# Rx_micro.net
KiCad netlist of a schematic drawn in Altium Designer
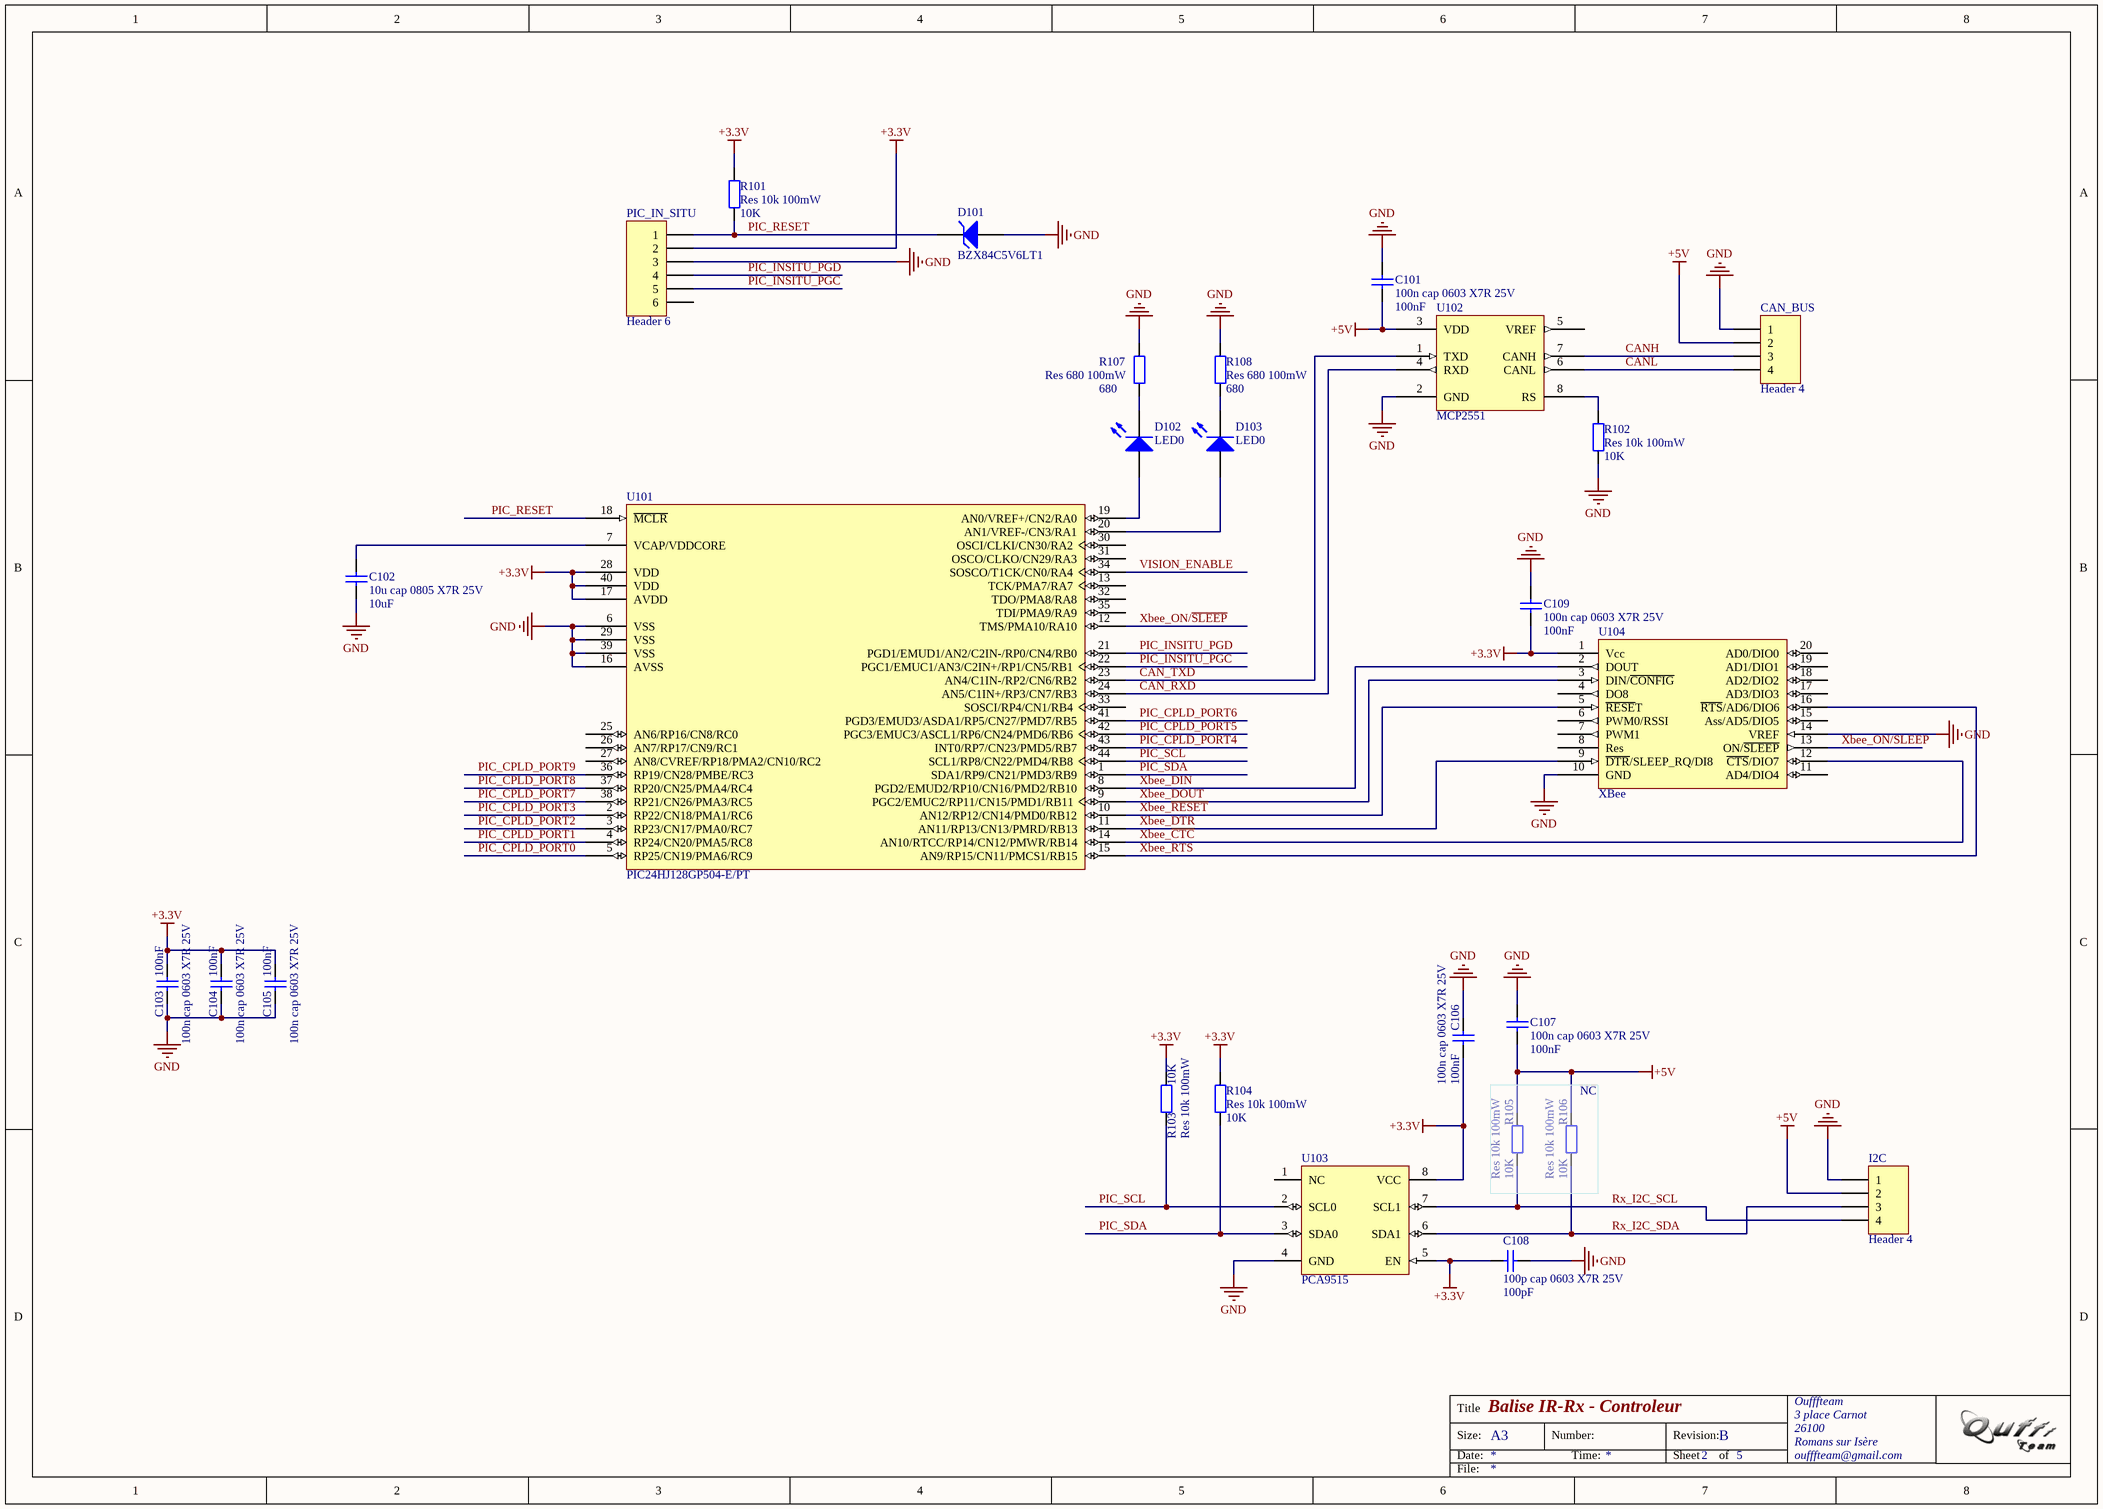
[diagram p0: Rx_micro.SchDoc]

(export (version "E")
  (design (tool "Eeschema 10.0.6"))
  (components
    (comp (ref "C101")
      (value "100n cap 0603 X7R 25V")
      (footprint "0603")
      (description "Capacitor")
      (fields (field (name "ALTIUM_VALUE") "100nF") (field (name "PUBLISHER") "Altium Limited"))
      (libsource (lib "Miscellaneous Devices") (part "Cap"))
    )
    (comp (ref "C102")
      (value "10u cap 0805 X7R 25V")
      (footprint "0805")
      (description "Capacitor")
      (fields (field (name "ALTIUM_VALUE") "10uF") (field (name "PUBLISHER") "Altium Limited"))
      (libsource (lib "Miscellaneous Devices") (part "Cap"))
    )
    (comp (ref "C103")
      (value "100n cap 0603 X7R 25V")
      (footprint "0603")
      (description "Capacitor")
      (fields (field (name "ALTIUM_VALUE") "100nF") (field (name "PUBLISHER") "Altium Limited"))
      (libsource (lib "Miscellaneous Devices") (part "Cap"))
    )
    (comp (ref "C104")
      (value "100n cap 0603 X7R 25V")
      (footprint "0603")
      (description "Capacitor")
      (fields (field (name "ALTIUM_VALUE") "100nF") (field (name "PUBLISHER") "Altium Limited"))
      (libsource (lib "Miscellaneous Devices") (part "Cap"))
    )
    (comp (ref "C105")
      (value "100n cap 0603 X7R 25V")
      (footprint "0603")
      (description "Capacitor")
      (fields (field (name "ALTIUM_VALUE") "100nF") (field (name "PUBLISHER") "Altium Limited"))
      (libsource (lib "Miscellaneous Devices") (part "Cap"))
    )
    (comp (ref "C106")
      (value "100n cap 0603 X7R 25V")
      (footprint "1608[0603]")
      (description "Capacitor")
      (fields (field (name "ALTIUM_VALUE") "100nF") (field (name "PUBLISHER") "Altium Limited"))
      (libsource (lib "Miscellaneous Devices") (part "Cap"))
    )
    (comp (ref "C107")
      (value "100n cap 0603 X7R 25V")
      (footprint "1608[0603]")
      (description "Capacitor")
      (fields (field (name "ALTIUM_VALUE") "100nF") (field (name "PUBLISHER") "Altium Limited"))
      (libsource (lib "Miscellaneous Devices") (part "Cap"))
    )
    (comp (ref "C108")
      (value "100p cap 0603 X7R 25V")
      (footprint "1608[0603]")
      (description "Capacitor")
      (fields (field (name "ALTIUM_VALUE") "100pF") (field (name "PUBLISHER") "Altium Limited"))
      (libsource (lib "Miscellaneous Devices") (part "Cap"))
    )
    (comp (ref "C109")
      (value "100n cap 0603 X7R 25V")
      (footprint "0603")
      (description "Capacitor")
      (fields (field (name "ALTIUM_VALUE") "100nF") (field (name "PUBLISHER") "Altium Limited"))
      (libsource (lib "Miscellaneous Devices") (part "Cap"))
    )
    (comp (ref "CAN_BUS")
      (value "Header 4")
      (footprint "HDR1X4")
      (description "Header, 4-Pin")
      (fields (field (name "PUBLISHER") "Altium Limited"))
      (libsource (lib "Miscellaneous Connectors") (part "Header 4"))
    )
    (comp (ref "D101")
      (value "BZX84C5V6LT1")
      (footprint "318-07")
      (description "Zener Voltage Regulator Diode")
      (fields (field (name "PUBLISHER") "Altium Limited"))
      (libsource (lib "Motorola Discrete Diode") (part "BZX84C5V6LT1"))
    )
    (comp (ref "D102")
      (value "LED0")
      (footprint "0603")
      (description "0603 Led")
      (fields (field (name "PUBLISHER") "Altium Limited"))
      (libsource (lib "Miscellaneous Devices") (part "LED0"))
    )
    (comp (ref "D103")
      (value "LED0")
      (footprint "0603")
      (description "0603 Led")
      (fields (field (name "PUBLISHER") "Altium Limited"))
      (libsource (lib "Miscellaneous Devices") (part "LED0"))
    )
    (comp (ref "I2C")
      (value "Header 4")
      (footprint "HDR1X4")
      (description "Header, 4-Pin")
      (fields (field (name "PUBLISHER") "Altium Limited"))
      (libsource (lib "Miscellaneous Connectors") (part "Header 4"))
    )
    (comp (ref "PIC_IN_SITU")
      (value "Header 6")
      (footprint "HDR1X6")
      (description "Header, 6-Pin")
      (fields (field (name "PUBLISHER") "Altium Limited"))
      (libsource (lib "Miscellaneous Connectors") (part "Header 6"))
    )
    (comp (ref "R101")
      (value "Res 10k 100mW")
      (footprint "0603")
      (description "Resistor")
      (fields (field (name "ALTIUM_VALUE") "10K") (field (name "PUBLISHER") "Altium Limited"))
      (libsource (lib "Miscellaneous Devices") (part "Res2"))
    )
    (comp (ref "R102")
      (value "Res 10k 100mW")
      (footprint "0603")
      (description "Resistor")
      (fields (field (name "ALTIUM_VALUE") "10K") (field (name "PUBLISHER") "Altium Limited"))
      (libsource (lib "Miscellaneous Devices") (part "Res2"))
    )
    (comp (ref "R103")
      (value "Res 10k 100mW")
      (footprint "0603")
      (description "Resistor")
      (fields (field (name "ALTIUM_VALUE") "10K") (field (name "PUBLISHER") "Altium Limited"))
      (libsource (lib "Miscellaneous Devices") (part "Res2"))
    )
    (comp (ref "R104")
      (value "Res 10k 100mW")
      (footprint "0603")
      (description "Resistor")
      (fields (field (name "ALTIUM_VALUE") "10K") (field (name "PUBLISHER") "Altium Limited"))
      (libsource (lib "Miscellaneous Devices") (part "Res2"))
    )
    (comp (ref "R105")
      (value "Res 10k 100mW")
      (footprint "1608[0603]")
      (description "Resistor")
      (fields (field (name "ALTIUM_VALUE") "10K") (field (name "PUBLISHER") "Altium Limited"))
      (libsource (lib "Miscellaneous Devices") (part "Res2"))
    )
    (comp (ref "R106")
      (value "Res 10k 100mW")
      (footprint "1608[0603]")
      (description "Resistor")
      (fields (field (name "ALTIUM_VALUE") "10K") (field (name "PUBLISHER") "Altium Limited"))
      (libsource (lib "Miscellaneous Devices") (part "Res2"))
    )
    (comp (ref "R107")
      (value "Res 680 100mW")
      (footprint "0603")
      (description "Resistor")
      (fields (field (name "ALTIUM_VALUE") "680") (field (name "PUBLISHER") "Altium Limited"))
      (libsource (lib "Miscellaneous Devices") (part "Res2"))
    )
    (comp (ref "R108")
      (value "Res 680 100mW")
      (footprint "0603")
      (description "Resistor")
      (fields (field (name "ALTIUM_VALUE") "680") (field (name "PUBLISHER") "Altium Limited"))
      (libsource (lib "Miscellaneous Devices") (part "Res2"))
    )
    (comp (ref "U101")
      (value "PIC24HJ128GP504-E/PT")
      (footprint "TQFP-PT44_N")
      (fields (field (name "PUBLISHER") "Altium Limited"))
      (libsource (lib "Microchip Microcontroller 16-Bit PIC24H") (part "PIC24HJ128GP504-E/PT"))
    )
    (comp (ref "U102")
      (value "MCP2551")
      (footprint "SOIC150-8_N")
      (description "High Speed Can Transceiver")
      (fields (field (name "PUBLISHER") "Altium Limited"))
      (libsource (lib "Microchip Interface Line Transceiver") (part "MCP2551"))
    )
    (comp (ref "U103")
      (value "PCA9515")
      (footprint "TSSOP-8")
      (description "DUAL BIDIRECTIONAL I2C BUS AND SMBus REPEATER")
      (libsource (lib "Oufff_Lib2") (part "PCA9515"))
    )
    (comp (ref "U104")
      (value "XBee")
      (footprint "XBee_SM")
      (description "OEM RF Modules")
      (libsource (lib "Oufff_Lib2") (part "XBee"))
    )
  )
  (nets
    (net (code "1") (name "+3.3V") (class "Default")
      (node (ref "C103") (pin "2") (pinfunction "2_2") (pintype "passive"))
      (node (ref "C104") (pin "2") (pinfunction "2_2") (pintype "passive"))
      (node (ref "C105") (pin "2") (pinfunction "2_2") (pintype "passive"))
      (node (ref "C106") (pin "1") (pinfunction "1_1") (pintype "passive"))
      (node (ref "C108") (pin "2") (pinfunction "2_2") (pintype "passive"))
      (node (ref "C109") (pin "1") (pinfunction "1_1") (pintype "passive"))
      (node (ref "PIC_IN_SITU") (pin "2") (pinfunction "2_2") (pintype "passive"))
      (node (ref "R101") (pin "2") (pinfunction "2_2") (pintype "passive"))
      (node (ref "R103") (pin "2") (pinfunction "2_2") (pintype "passive"))
      (node (ref "R104") (pin "2") (pinfunction "2_2") (pintype "passive"))
      (node (ref "U101") (pin "17") (pinfunction "AVDD_17") (pintype "power_in"))
      (node (ref "U101") (pin "28") (pinfunction "VDD_28") (pintype "power_in"))
      (node (ref "U101") (pin "40") (pinfunction "VDD_40") (pintype "power_in"))
      (node (ref "U103") (pin "5") (pinfunction "EN_5") (pintype "input"))
      (node (ref "U103") (pin "8") (pinfunction "VCC_8") (pintype "power_in"))
      (node (ref "U104") (pin "1") (pinfunction "Vcc_1") (pintype "power_in"))
    )
    (net (code "2") (name "+5V") (class "Default")
      (node (ref "C101") (pin "1") (pinfunction "1_1") (pintype "passive"))
      (node (ref "C107") (pin "2") (pinfunction "2_2") (pintype "passive"))
      (node (ref "CAN_BUS") (pin "2") (pinfunction "2_2") (pintype "passive"))
      (node (ref "I2C") (pin "2") (pinfunction "2_2") (pintype "passive"))
      (node (ref "R105") (pin "2") (pinfunction "2_2") (pintype "passive"))
      (node (ref "R106") (pin "2") (pinfunction "2_2") (pintype "passive"))
      (node (ref "U102") (pin "3") (pinfunction "VDD_3") (pintype "power_in"))
    )
    (net (code "3") (name "/CANH") (class "Default")
      (node (ref "CAN_BUS") (pin "3") (pinfunction "3_3") (pintype "passive"))
      (node (ref "U102") (pin "7") (pinfunction "CANH_7") (pintype "output"))
    )
    (net (code "4") (name "/CANL") (class "Default")
      (node (ref "CAN_BUS") (pin "4") (pinfunction "4_4") (pintype "passive"))
      (node (ref "U102") (pin "6") (pinfunction "CANL_6") (pintype "output"))
    )
    (net (code "5") (name "/CAN_RXD") (class "Default")
      (node (ref "U101") (pin "24") (pinfunction "AN5/C1IN+/RP3/CN7/RB3_24") (pintype "bidirectional"))
      (node (ref "U102") (pin "4") (pinfunction "RXD_4") (pintype "output"))
    )
    (net (code "6") (name "/CAN_TXD") (class "Default")
      (node (ref "U101") (pin "23") (pinfunction "AN4/C1IN-/RP2/CN6/RB2_23") (pintype "bidirectional"))
      (node (ref "U102") (pin "1") (pinfunction "TXD_1") (pintype "input"))
    )
    (net (code "7") (name "/PIC_CPLD_PORT0") (class "Default")
      (node (ref "U101") (pin "5") (pinfunction "RP25/CN19/PMA6/RC9_5") (pintype "bidirectional"))
    )
    (net (code "8") (name "/PIC_CPLD_PORT1") (class "Default")
      (node (ref "U101") (pin "4") (pinfunction "RP24/CN20/PMA5/RC8_4") (pintype "bidirectional"))
    )
    (net (code "9") (name "/PIC_CPLD_PORT2") (class "Default")
      (node (ref "U101") (pin "3") (pinfunction "RP23/CN17/PMA0/RC7_3") (pintype "bidirectional"))
    )
    (net (code "10") (name "/PIC_CPLD_PORT3") (class "Default")
      (node (ref "U101") (pin "2") (pinfunction "RP22/CN18/PMA1/RC6_2") (pintype "bidirectional"))
    )
    (net (code "11") (name "/PIC_CPLD_PORT4") (class "Default")
      (node (ref "U101") (pin "43") (pinfunction "INT0/RP7/CN23/PMD5/RB7_43") (pintype "bidirectional"))
    )
    (net (code "12") (name "/PIC_CPLD_PORT5") (class "Default")
      (node (ref "U101") (pin "42") (pinfunction "PGC3/EMUC3/ASCL1/RP6/CN24/PMD6/RB6_42") (pintype "bidirectional"))
    )
    (net (code "13") (name "/PIC_CPLD_PORT6") (class "Default")
      (node (ref "U101") (pin "41") (pinfunction "PGD3/EMUD3/ASDA1/RP5/CN27/PMD7/RB5_41") (pintype "bidirectional"))
    )
    (net (code "14") (name "/PIC_CPLD_PORT7") (class "Default")
      (node (ref "U101") (pin "38") (pinfunction "RP21/CN26/PMA3/RC5_38") (pintype "bidirectional"))
    )
    (net (code "15") (name "/PIC_CPLD_PORT8") (class "Default")
      (node (ref "U101") (pin "37") (pinfunction "RP20/CN25/PMA4/RC4_37") (pintype "bidirectional"))
    )
    (net (code "16") (name "/PIC_CPLD_PORT9") (class "Default")
      (node (ref "U101") (pin "36") (pinfunction "RP19/CN28/PMBE/RC3_36") (pintype "bidirectional"))
    )
    (net (code "17") (name "/PIC_INSITU_PGC") (class "Default")
      (node (ref "PIC_IN_SITU") (pin "5") (pinfunction "5_5") (pintype "passive"))
      (node (ref "U101") (pin "22") (pinfunction "PGC1/EMUC1/AN3/C2IN+/RP1/CN5/RB1_22") (pintype "bidirectional"))
    )
    (net (code "18") (name "/PIC_INSITU_PGD") (class "Default")
      (node (ref "PIC_IN_SITU") (pin "4") (pinfunction "4_4") (pintype "passive"))
      (node (ref "U101") (pin "21") (pinfunction "PGD1/EMUD1/AN2/C2IN-/RP0/CN4/RB0_21") (pintype "bidirectional"))
    )
    (net (code "19") (name "/PIC_RESET") (class "Default")
      (node (ref "D101") (pin "3") (pinfunction "K_3") (pintype "passive"))
      (node (ref "PIC_IN_SITU") (pin "1") (pinfunction "1_1") (pintype "passive"))
      (node (ref "R101") (pin "1") (pinfunction "1_1") (pintype "passive"))
      (node (ref "U101") (pin "18") (pinfunction "~{MCLR}_18") (pintype "input"))
    )
    (net (code "20") (name "/PIC_SCL") (class "Default")
      (node (ref "R103") (pin "1") (pinfunction "1_1") (pintype "passive"))
      (node (ref "U101") (pin "44") (pinfunction "SCL1/RP8/CN22/PMD4/RB8_44") (pintype "bidirectional"))
      (node (ref "U103") (pin "2") (pinfunction "SCL0_2") (pintype "bidirectional"))
    )
    (net (code "21") (name "/PIC_SDA") (class "Default")
      (node (ref "R104") (pin "1") (pinfunction "1_1") (pintype "passive"))
      (node (ref "U101") (pin "1") (pinfunction "SDA1/RP9/CN21/PMD3/RB9_1") (pintype "bidirectional"))
      (node (ref "U103") (pin "3") (pinfunction "SDA0_3") (pintype "bidirectional"))
    )
    (net (code "22") (name "/Rx_I2C_SCL") (class "Default")
      (node (ref "I2C") (pin "4") (pinfunction "4_4") (pintype "passive"))
      (node (ref "R105") (pin "1") (pinfunction "1_1") (pintype "passive"))
      (node (ref "U103") (pin "7") (pinfunction "SCL1_7") (pintype "bidirectional"))
    )
    (net (code "23") (name "/Rx_I2C_SDA") (class "Default")
      (node (ref "I2C") (pin "3") (pinfunction "3_3") (pintype "passive"))
      (node (ref "R106") (pin "1") (pinfunction "1_1") (pintype "passive"))
      (node (ref "U103") (pin "6") (pinfunction "SDA1_6") (pintype "bidirectional"))
    )
    (net (code "24") (name "/VISION_ENABLE") (class "Default")
      (node (ref "U101") (pin "34") (pinfunction "SOSCO/T1CK/CN0/RA4_34") (pintype "bidirectional"))
    )
    (net (code "25") (name "/Xbee_DIN") (class "Default")
      (node (ref "U101") (pin "8") (pinfunction "PGD2/EMUD2/RP10/CN16/PMD2/RB10_8") (pintype "bidirectional"))
      (node (ref "U104") (pin "2") (pinfunction "DOUT_2") (pintype "output"))
    )
    (net (code "26") (name "/Xbee_DOUT") (class "Default")
      (node (ref "U101") (pin "9") (pinfunction "PGC2/EMUC2/RP11/CN15/PMD1/RB11_9") (pintype "bidirectional"))
      (node (ref "U104") (pin "3") (pinfunction "DIN/~{CONFIG}_3") (pintype "input"))
    )
    (net (code "27") (name "/Xbee_DTR") (class "Default")
      (node (ref "U101") (pin "11") (pinfunction "AN11/RP13/CN13/PMRD/RB13_11") (pintype "bidirectional"))
      (node (ref "U104") (pin "9") (pinfunction "~{DTR}/SLEEP_RQ/DI8_9") (pintype "input"))
    )
    (net (code "28") (name "/Xbee_ON{slash}~{SLEEP}") (class "Default")
      (node (ref "U101") (pin "12") (pinfunction "TMS/PMA10/RA10_12") (pintype "bidirectional"))
      (node (ref "U104") (pin "13") (pinfunction "ON/~{SLEEP}_13") (pintype "output"))
    )
    (net (code "29") (name "/Xbee_~{CTC}") (class "Default")
      (node (ref "U101") (pin "14") (pinfunction "AN10/RTCC/RP14/CN12/PMWR/RB14_14") (pintype "bidirectional"))
      (node (ref "U104") (pin "12") (pinfunction "~{CTS}/DIO7_12") (pintype "bidirectional"))
    )
    (net (code "30") (name "/Xbee_~{RESET}") (class "Default")
      (node (ref "U101") (pin "10") (pinfunction "AN12/RP12/CN14/PMD0/RB12_10") (pintype "bidirectional"))
      (node (ref "U104") (pin "5") (pinfunction "~{RESE}T_5") (pintype "input"))
    )
    (net (code "31") (name "/Xbee_~{RTS}") (class "Default")
      (node (ref "U101") (pin "15") (pinfunction "AN9/RP15/CN11/PMCS1/RB15_15") (pintype "bidirectional"))
      (node (ref "U104") (pin "16") (pinfunction "~{RTS}/AD6/DIO6_16") (pintype "bidirectional"))
    )
    (net (code "32") (name "GND") (class "Default")
      (node (ref "C101") (pin "2") (pinfunction "2_2") (pintype "passive"))
      (node (ref "C102") (pin "1") (pinfunction "1_1") (pintype "passive"))
      (node (ref "C103") (pin "1") (pinfunction "1_1") (pintype "passive"))
      (node (ref "C104") (pin "1") (pinfunction "1_1") (pintype "passive"))
      (node (ref "C105") (pin "1") (pinfunction "1_1") (pintype "passive"))
      (node (ref "C106") (pin "2") (pinfunction "2_2") (pintype "passive"))
      (node (ref "C107") (pin "1") (pinfunction "1_1") (pintype "passive"))
      (node (ref "C108") (pin "1") (pinfunction "1_1") (pintype "passive"))
      (node (ref "C109") (pin "2") (pinfunction "2_2") (pintype "passive"))
      (node (ref "CAN_BUS") (pin "1") (pinfunction "1_1") (pintype "passive"))
      (node (ref "D101") (pin "1") (pinfunction "A_1") (pintype "passive"))
      (node (ref "I2C") (pin "1") (pinfunction "1_1") (pintype "passive"))
      (node (ref "PIC_IN_SITU") (pin "3") (pinfunction "3_3") (pintype "passive"))
      (node (ref "R102") (pin "1") (pinfunction "1_1") (pintype "passive"))
      (node (ref "R107") (pin "2") (pinfunction "2_2") (pintype "passive"))
      (node (ref "R108") (pin "2") (pinfunction "2_2") (pintype "passive"))
      (node (ref "U101") (pin "16") (pinfunction "AVSS_16") (pintype "power_in"))
      (node (ref "U101") (pin "29") (pinfunction "VSS_29") (pintype "power_in"))
      (node (ref "U101") (pin "39") (pinfunction "VSS_39") (pintype "power_in"))
      (node (ref "U101") (pin "6") (pinfunction "VSS_6") (pintype "power_in"))
      (node (ref "U102") (pin "2") (pinfunction "GND_2") (pintype "power_in"))
      (node (ref "U103") (pin "4") (pinfunction "GND_4") (pintype "power_in"))
      (node (ref "U104") (pin "10") (pinfunction "GND_10") (pintype "power_in"))
      (node (ref "U104") (pin "14") (pinfunction "VREF_14") (pintype "input"))
    )
    (net (code "33") (name "Net-(D102-A)") (class "Default")
      (node (ref "D102") (pin "1") (pinfunction "A_1") (pintype "passive"))
      (node (ref "U101") (pin "19") (pinfunction "AN0/VREF+/CN2/RA0_19") (pintype "bidirectional"))
    )
    (net (code "34") (name "Net-(D102-K)") (class "Default")
      (node (ref "D102") (pin "2") (pinfunction "K_2") (pintype "passive"))
      (node (ref "R107") (pin "1") (pinfunction "1_1") (pintype "passive"))
    )
    (net (code "35") (name "Net-(D103-A)") (class "Default")
      (node (ref "D103") (pin "1") (pinfunction "A_1") (pintype "passive"))
      (node (ref "U101") (pin "20") (pinfunction "AN1/VREF-/CN3/RA1_20") (pintype "bidirectional"))
    )
    (net (code "36") (name "Net-(D103-K)") (class "Default")
      (node (ref "D103") (pin "2") (pinfunction "K_2") (pintype "passive"))
      (node (ref "R108") (pin "1") (pinfunction "1_1") (pintype "passive"))
    )
    (net (code "37") (name "Net-(U101-VCAP{slash}VDDCORE)") (class "Default")
      (node (ref "C102") (pin "2") (pinfunction "2_2") (pintype "passive"))
      (node (ref "U101") (pin "7") (pinfunction "VCAP/VDDCORE_7") (pintype "power_in"))
    )
    (net (code "38") (name "Net-(U102-RS)") (class "Default")
      (node (ref "R102") (pin "2") (pinfunction "2_2") (pintype "passive"))
      (node (ref "U102") (pin "8") (pinfunction "RS_8") (pintype "passive"))
    )
    (net (code "39") (name "unconnected-(PIC_IN_SITU-Pad6)") (class "Default")
      (node (ref "PIC_IN_SITU") (pin "6") (pinfunction "6_6") (pintype "passive"))
    )
    (net (code "40") (name "unconnected-(U101-AN6{slash}RP16{slash}CN8{slash}RC0-Pad25)") (class "Default")
      (node (ref "U101") (pin "25") (pinfunction "AN6/RP16/CN8/RC0_25") (pintype "bidirectional"))
    )
    (net (code "41") (name "unconnected-(U101-AN7{slash}RP17{slash}CN9{slash}RC1-Pad26)") (class "Default")
      (node (ref "U101") (pin "26") (pinfunction "AN7/RP17/CN9/RC1_26") (pintype "bidirectional"))
    )
    (net (code "42") (name "unconnected-(U101-AN8{slash}CVREF{slash}RP18{slash}PMA2{slash}CN10{slash}RC2-Pad27)") (class "Default")
      (node (ref "U101") (pin "27") (pinfunction "AN8/CVREF/RP18/PMA2/CN10/RC2_27") (pintype "bidirectional"))
    )
    (net (code "43") (name "unconnected-(U101-OSCI{slash}CLKI{slash}CN30{slash}RA2-Pad30)") (class "Default")
      (node (ref "U101") (pin "30") (pinfunction "OSCI/CLKI/CN30/RA2_30") (pintype "bidirectional"))
    )
    (net (code "44") (name "unconnected-(U101-OSCO{slash}CLKO{slash}CN29{slash}RA3-Pad31)") (class "Default")
      (node (ref "U101") (pin "31") (pinfunction "OSCO/CLKO/CN29/RA3_31") (pintype "bidirectional"))
    )
    (net (code "45") (name "unconnected-(U101-SOSCI{slash}RP4{slash}CN1{slash}RB4-Pad33)") (class "Default")
      (node (ref "U101") (pin "33") (pinfunction "SOSCI/RP4/CN1/RB4_33") (pintype "bidirectional"))
    )
    (net (code "46") (name "unconnected-(U101-TCK{slash}PMA7{slash}RA7-Pad13)") (class "Default")
      (node (ref "U101") (pin "13") (pinfunction "TCK/PMA7/RA7_13") (pintype "bidirectional"))
    )
    (net (code "47") (name "unconnected-(U101-TDI{slash}PMA9{slash}RA9-Pad35)") (class "Default")
      (node (ref "U101") (pin "35") (pinfunction "TDI/PMA9/RA9_35") (pintype "bidirectional"))
    )
    (net (code "48") (name "unconnected-(U101-TDO{slash}PMA8{slash}RA8-Pad32)") (class "Default")
      (node (ref "U101") (pin "32") (pinfunction "TDO/PMA8/RA8_32") (pintype "bidirectional"))
    )
    (net (code "49") (name "unconnected-(U102-VREF-Pad5)") (class "Default")
      (node (ref "U102") (pin "5") (pinfunction "VREF_5") (pintype "output"))
    )
    (net (code "50") (name "unconnected-(U103-NC-Pad1)") (class "Default")
      (node (ref "U103") (pin "1") (pinfunction "NC_1") (pintype "passive"))
    )
    (net (code "51") (name "unconnected-(U104-AD0{slash}DIO0-Pad20)") (class "Default")
      (node (ref "U104") (pin "20") (pinfunction "AD0/DIO0_20") (pintype "bidirectional"))
    )
    (net (code "52") (name "unconnected-(U104-AD1{slash}DIO1-Pad19)") (class "Default")
      (node (ref "U104") (pin "19") (pinfunction "AD1/DIO1_19") (pintype "bidirectional"))
    )
    (net (code "53") (name "unconnected-(U104-AD2{slash}DIO2-Pad18)") (class "Default")
      (node (ref "U104") (pin "18") (pinfunction "AD2/DIO2_18") (pintype "bidirectional"))
    )
    (net (code "54") (name "unconnected-(U104-AD3{slash}DIO3-Pad17)") (class "Default")
      (node (ref "U104") (pin "17") (pinfunction "AD3/DIO3_17") (pintype "bidirectional"))
    )
    (net (code "55") (name "unconnected-(U104-AD4{slash}DIO4-Pad11)") (class "Default")
      (node (ref "U104") (pin "11") (pinfunction "AD4/DIO4_11") (pintype "bidirectional"))
    )
    (net (code "56") (name "unconnected-(U104-Ass{slash}AD5{slash}DIO5-Pad15)") (class "Default")
      (node (ref "U104") (pin "15") (pinfunction "Ass/AD5/DIO5_15") (pintype "bidirectional"))
    )
    (net (code "57") (name "unconnected-(U104-DO8-Pad4)") (class "Default")
      (node (ref "U104") (pin "4") (pinfunction "DO8_4") (pintype "output"))
    )
    (net (code "58") (name "unconnected-(U104-PWM0{slash}RSSI-Pad6)") (class "Default")
      (node (ref "U104") (pin "6") (pinfunction "PWM0/RSSI_6") (pintype "output"))
    )
    (net (code "59") (name "unconnected-(U104-PWM1-Pad7)") (class "Default")
      (node (ref "U104") (pin "7") (pinfunction "PWM1_7") (pintype "output"))
    )
    (net (code "60") (name "unconnected-(U104-Res-Pad8)") (class "Default")
      (node (ref "U104") (pin "8") (pinfunction "Res_8") (pintype "passive"))
    )
  )
)
